# ESP32_with_USBC.net
KiCad netlist of a schematic drawn in Altium Designer
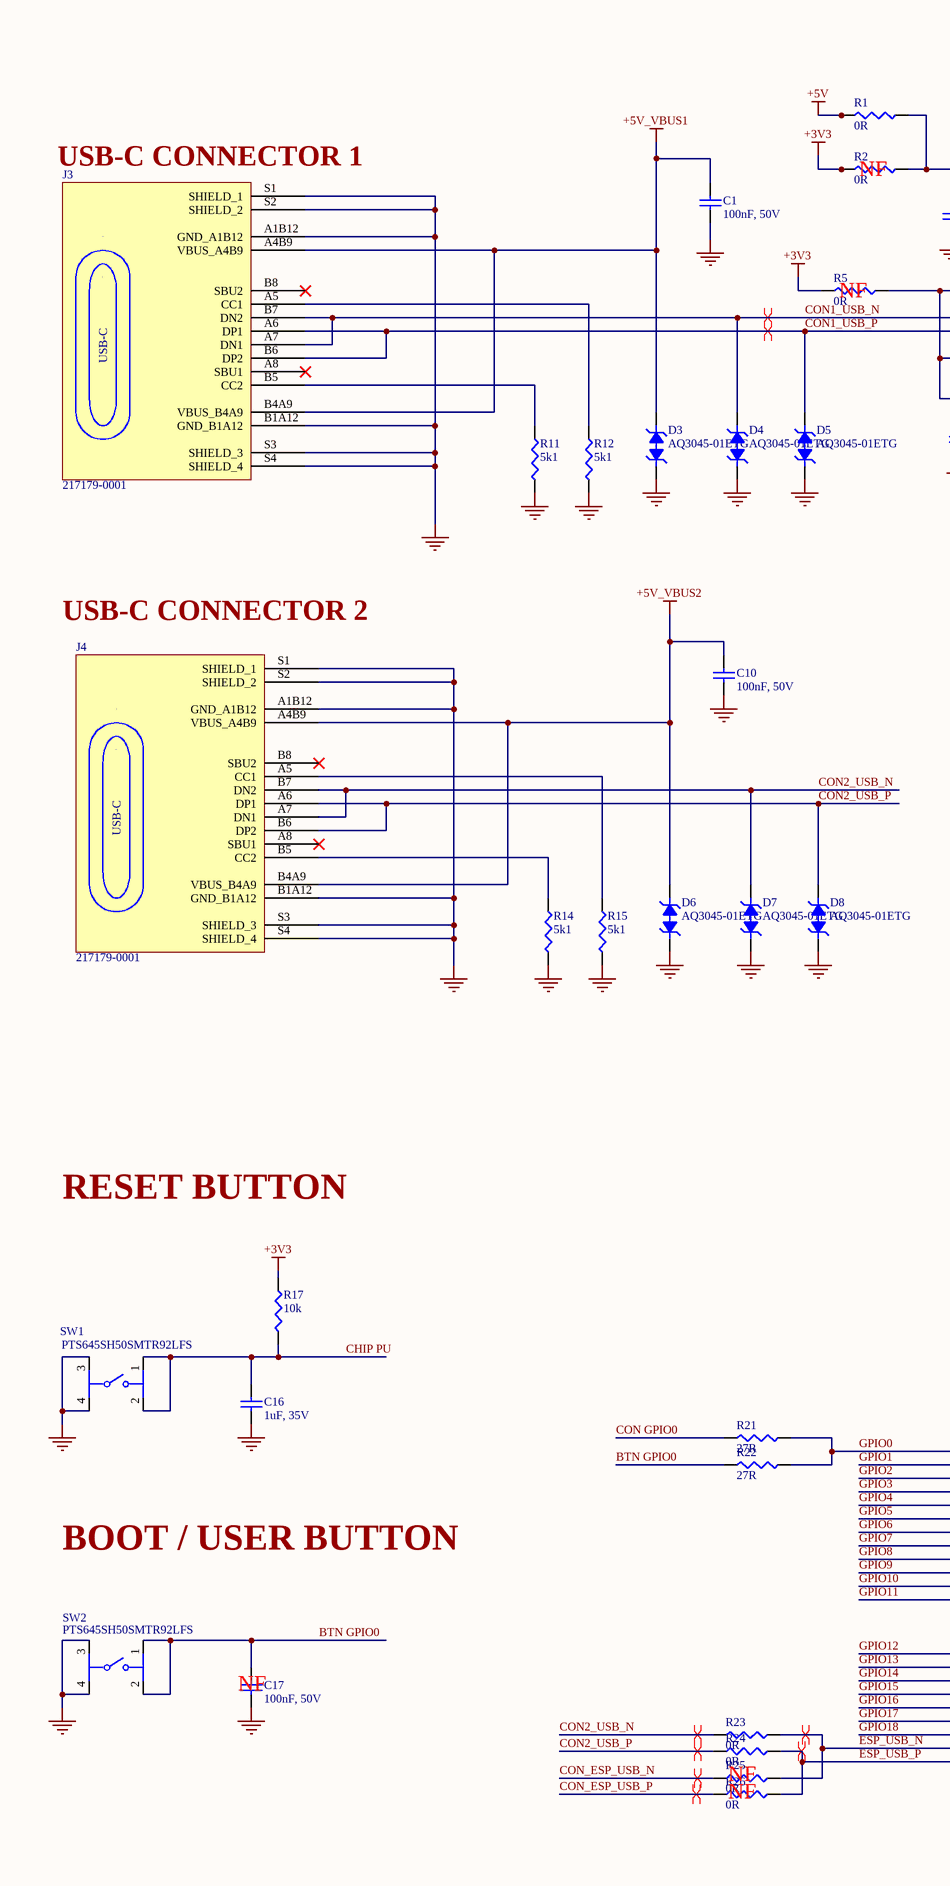
[diagram p0: ESP32 with USBC.SchDoc, left]
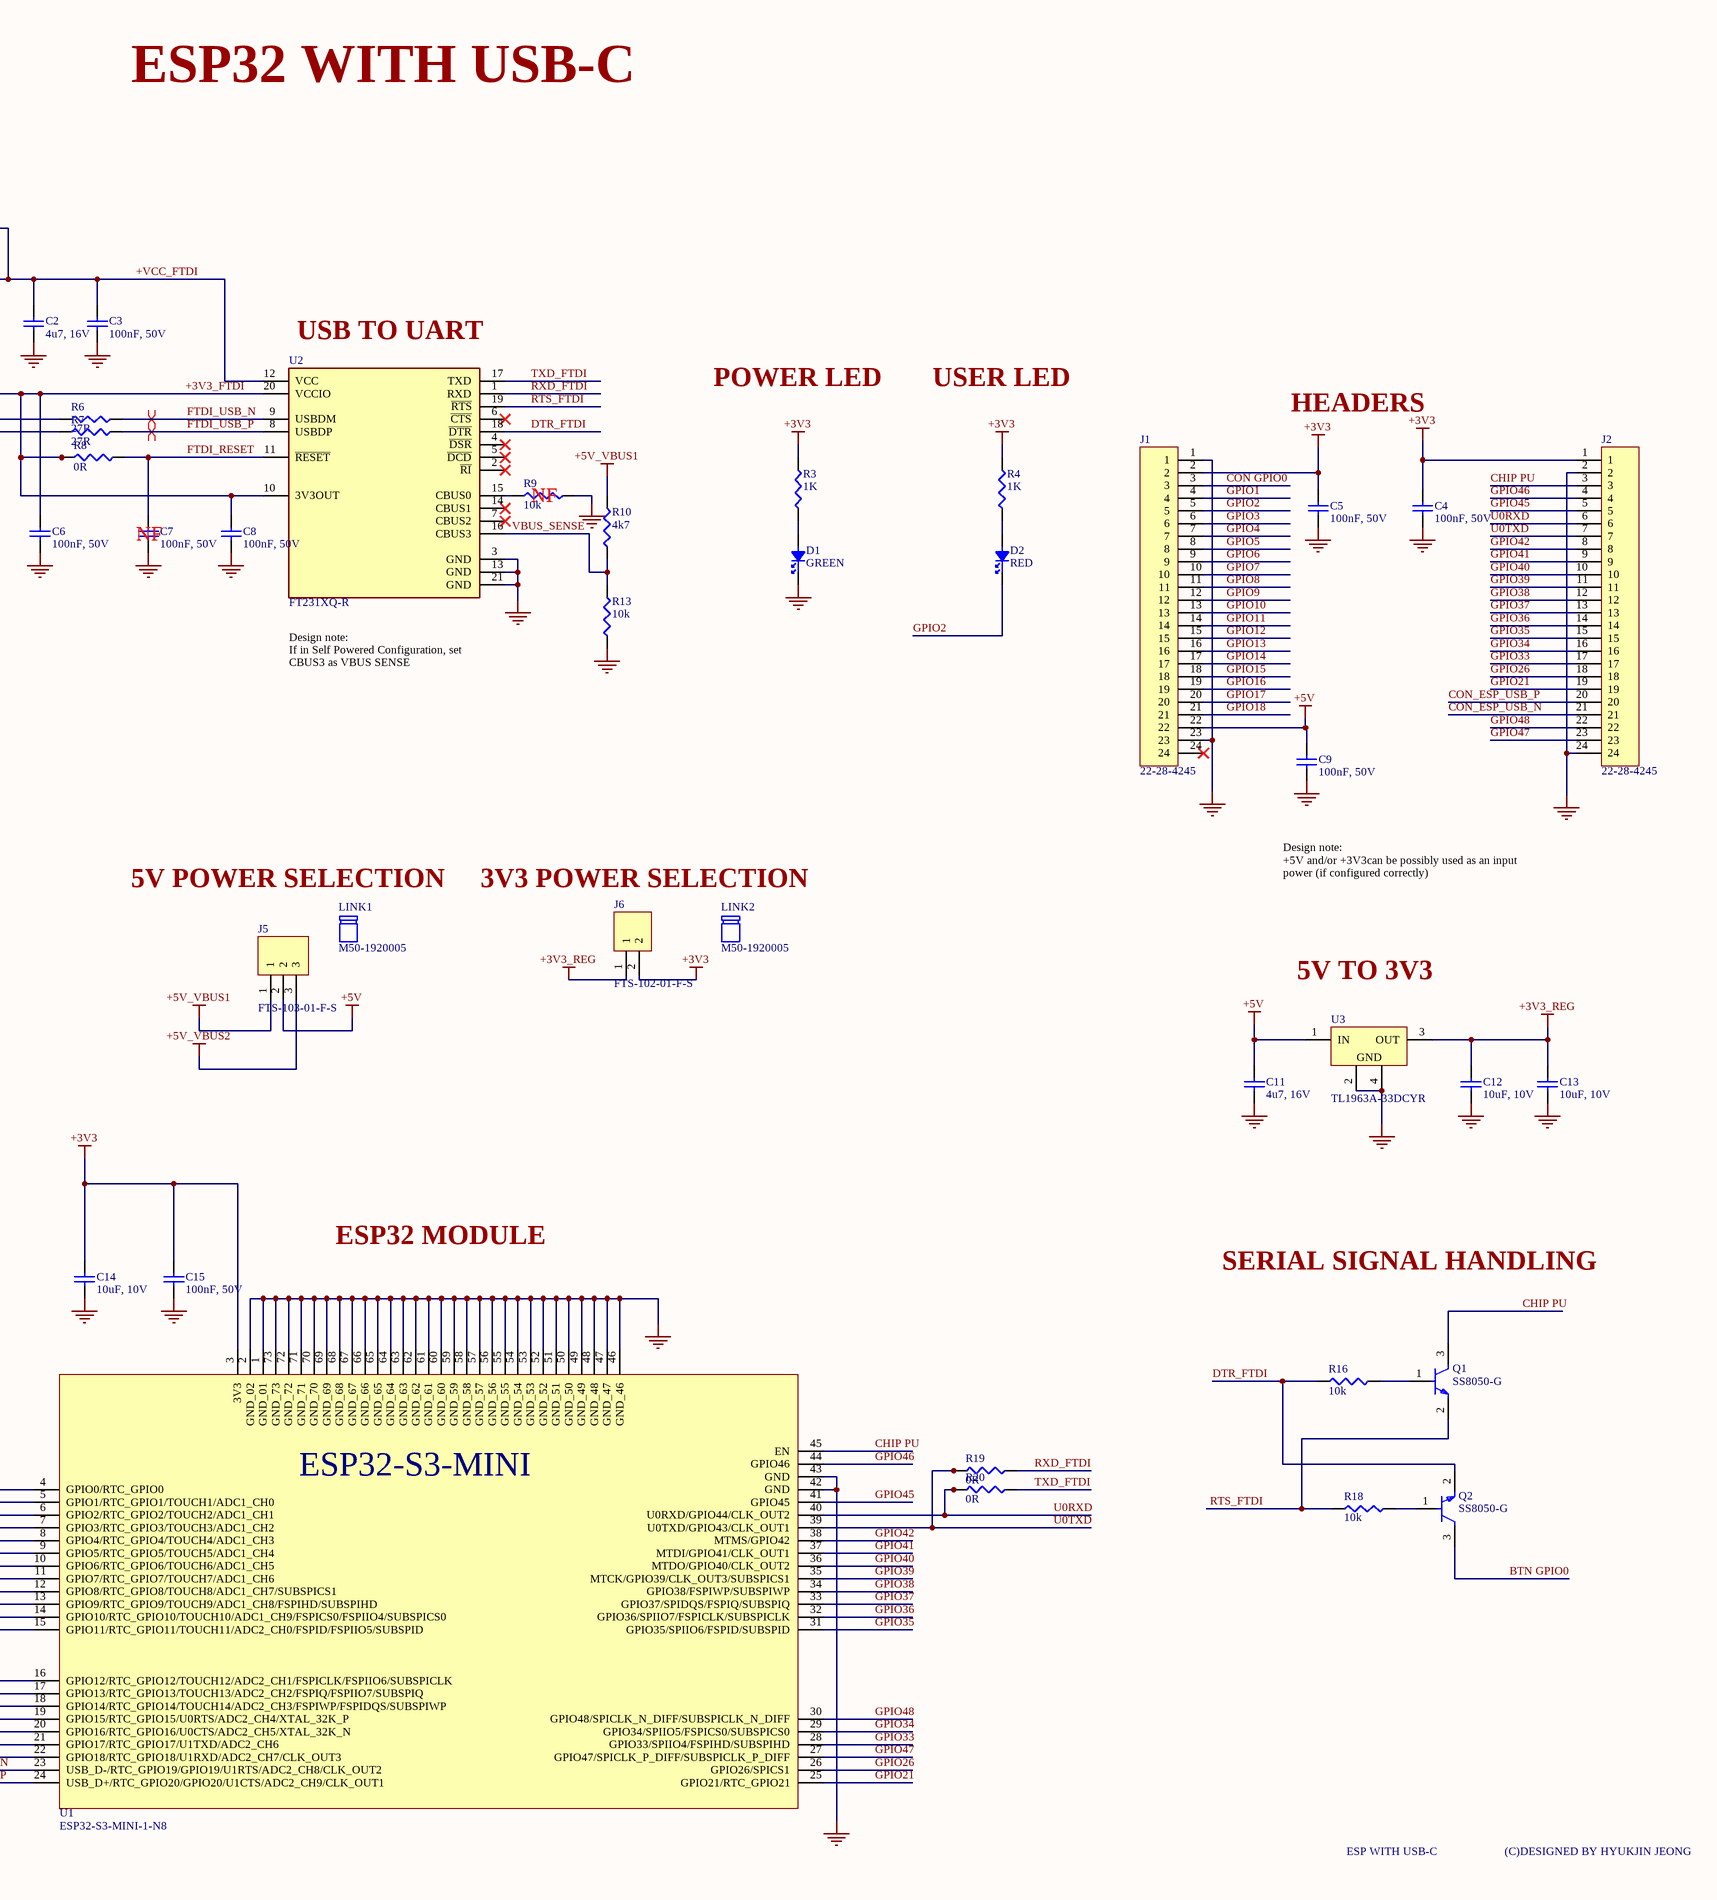
[diagram p1: ESP32 with USBC.SchDoc, right]

(export (version "E")
  (design (tool "Eeschema 10.0.6"))
  (components
    (comp (ref "C1")
      (value "100nF, 50V")
      (footprint "CAPC1005X65N")
      (description "CAP CER 0.1UF 50V X7R 0402")
      (fields
        (field (name "MANUFACTURER") "Samsung Electro-Mechanics")
        (field (name "MANUFACTURER PART NUMBER") "CL05B104KB54PNC")
      )
      (libsource (lib "Schlib") (part "CL05B104KB54PNC"))
    )
    (comp (ref "C2")
      (value "4u7, 16V")
      (footprint "CAPC1005X65N")
      (description "CAP CER 4.7UF 16V X5R 0402")
      (fields
        (field (name "MANUFACTURER") "Samsung Electro-Mechanics")
        (field (name "MANUFACTURER PART NUMBER") "CL05A475MO5NUNC")
      )
      (libsource (lib "Schlib") (part "CL05A475MO5NUNC"))
    )
    (comp (ref "C3")
      (value "100nF, 50V")
      (footprint "CAPC1005X65N")
      (description "CAP CER 0.1UF 50V X7R 0402")
      (fields
        (field (name "MANUFACTURER") "Samsung Electro-Mechanics")
        (field (name "MANUFACTURER PART NUMBER") "CL05B104KB54PNC")
      )
      (libsource (lib "Schlib") (part "CL05B104KB54PNC"))
    )
    (comp (ref "C4")
      (value "100nF, 50V")
      (footprint "CAPC1005X65N")
      (description "CAP CER 0.1UF 50V X7R 0402")
      (fields
        (field (name "MANUFACTURER") "Samsung Electro-Mechanics")
        (field (name "MANUFACTURER PART NUMBER") "CL05B104KB54PNC")
      )
      (libsource (lib "Schlib") (part "CL05B104KB54PNC"))
    )
    (comp (ref "C5")
      (value "100nF, 50V")
      (footprint "CAPC1005X65N")
      (description "CAP CER 0.1UF 50V X7R 0402")
      (fields
        (field (name "MANUFACTURER") "Samsung Electro-Mechanics")
        (field (name "MANUFACTURER PART NUMBER") "CL05B104KB54PNC")
      )
      (libsource (lib "Schlib") (part "CL05B104KB54PNC"))
    )
    (comp (ref "C6")
      (value "100nF, 50V")
      (footprint "CAPC1005X65N")
      (description "CAP CER 0.1UF 50V X7R 0402")
      (fields
        (field (name "MANUFACTURER") "Samsung Electro-Mechanics")
        (field (name "MANUFACTURER PART NUMBER") "CL05B104KB54PNC")
      )
      (libsource (lib "Schlib") (part "CL05B104KB54PNC"))
    )
    (comp (ref "C7")
      (value "100nF, 50V")
      (footprint "CAPC1005X65N")
      (description "CAP CER 0.1UF 50V X7R 0402")
      (fields
        (field (name "MANUFACTURER") "Samsung Electro-Mechanics")
        (field (name "MANUFACTURER PART NUMBER") "CL05B104KB54PNC")
      )
      (libsource (lib "Schlib") (part "CL05B104KB54PNC"))
    )
    (comp (ref "C8")
      (value "100nF, 50V")
      (footprint "CAPC1005X65N")
      (description "CAP CER 0.1UF 50V X7R 0402")
      (fields
        (field (name "MANUFACTURER") "Samsung Electro-Mechanics")
        (field (name "MANUFACTURER PART NUMBER") "CL05B104KB54PNC")
      )
      (libsource (lib "Schlib") (part "CL05B104KB54PNC"))
    )
    (comp (ref "C9")
      (value "100nF, 50V")
      (footprint "CAPC1005X65N")
      (description "CAP CER 0.1UF 50V X7R 0402")
      (fields
        (field (name "MANUFACTURER") "Samsung Electro-Mechanics")
        (field (name "MANUFACTURER PART NUMBER") "CL05B104KB54PNC")
      )
      (libsource (lib "Schlib") (part "CL05B104KB54PNC"))
    )
    (comp (ref "C10")
      (value "100nF, 50V")
      (footprint "CAPC1005X65N")
      (description "CAP CER 0.1UF 50V X7R 0402")
      (fields
        (field (name "MANUFACTURER") "Samsung Electro-Mechanics")
        (field (name "MANUFACTURER PART NUMBER") "CL05B104KB54PNC")
      )
      (libsource (lib "Schlib") (part "CL05B104KB54PNC"))
    )
    (comp (ref "C11")
      (value "4u7, 16V")
      (footprint "CAPC1005X65N")
      (description "CAP CER 4.7UF 16V X5R 0402")
      (fields
        (field (name "MANUFACTURER") "Samsung Electro-Mechanics")
        (field (name "MANUFACTURER PART NUMBER") "CL05A475MO5NUNC")
      )
      (libsource (lib "Schlib") (part "CL05A475MO5NUNC"))
    )
    (comp (ref "C12")
      (value "10uF, 10V")
      (footprint "CAPC1005X65N")
      (description "CAP CER 10UF 10V X5R 0402")
      (fields
        (field (name "MANUFACTURER") "Samsung Electro-Mechanics")
        (field (name "MANUFACTURER PART NUMBER") "CL05A106MP8NUB8")
      )
      (libsource (lib "Schlib") (part "CL05A106MP8NUB8"))
    )
    (comp (ref "C13")
      (value "10uF, 10V")
      (footprint "CAPC1005X65N")
      (description "CAP CER 10UF 10V X5R 0402")
      (fields
        (field (name "MANUFACTURER") "Samsung Electro-Mechanics")
        (field (name "MANUFACTURER PART NUMBER") "CL05A106MP8NUB8")
      )
      (libsource (lib "Schlib") (part "CL05A106MP8NUB8"))
    )
    (comp (ref "C14")
      (value "10uF, 10V")
      (footprint "CAPC1005X65N")
      (description "CAP CER 10UF 10V X5R 0402")
      (fields
        (field (name "MANUFACTURER") "Samsung Electro-Mechanics")
        (field (name "MANUFACTURER PART NUMBER") "CL05A106MP8NUB8")
      )
      (libsource (lib "Schlib") (part "CL05A106MP8NUB8"))
    )
    (comp (ref "C15")
      (value "100nF, 50V")
      (footprint "CAPC1005X65N")
      (description "CAP CER 0.1UF 50V X7R 0402")
      (fields
        (field (name "MANUFACTURER") "Samsung Electro-Mechanics")
        (field (name "MANUFACTURER PART NUMBER") "CL05B104KB54PNC")
      )
      (libsource (lib "Schlib") (part "CL05B104KB54PNC"))
    )
    (comp (ref "C16")
      (value "1uF, 35V")
      (footprint "CAPC1005X65N")
      (description "CAP CER 1UF 35V X5R 0402")
      (fields
        (field (name "MANUFACTURER") "Samsung Electro-Mechanics")
        (field (name "MANUFACTURER PART NUMBER") "CL05A105KL5NRNC")
      )
      (libsource (lib "Schlib") (part "CL05A105KL5NRNC"))
    )
    (comp (ref "C17")
      (value "100nF, 50V")
      (footprint "CAPC1005X65N")
      (description "CAP CER 0.1UF 50V X7R 0402")
      (fields
        (field (name "MANUFACTURER") "Samsung Electro-Mechanics")
        (field (name "MANUFACTURER PART NUMBER") "CL05B104KB54PNC")
      )
      (libsource (lib "Schlib") (part "CL05B104KB54PNC"))
    )
    (comp (ref "D1")
      (value "GREEN")
      (footprint "LED0402G")
      (description "LED YLW-GRN 0402 SMD")
      (fields
        (field (name "MANUFACTURER") "Vishay")
        (field (name "MANUFACTURER PART NUMBER") "VLMG1500-GS08")
      )
      (libsource (lib "Schlib") (part "VLMG1500-GS08"))
    )
    (comp (ref "D2")
      (value "RED")
      (footprint "LED0402R")
      (description "LED RED 0402 SMD")
      (fields
        (field (name "MANUFACTURER") "Vishay")
        (field (name "MANUFACTURER PART NUMBER") "VLMS1500-GS08")
      )
      (libsource (lib "Schlib") (part "VLMS1500-GS08"))
    )
    (comp (ref "D3")
      (value "AQ3045-01ETG")
      (footprint "SOD882")
      (description "TVS DIODE 5.3VWM 12VC SOD882")
      (fields (field (name "MANUFACTURER") "Littelfuse") (field (name "LCSC PART NUMBER") "C3710326"))
      (libsource (lib "Schlib") (part "AQ3045-01ETG"))
    )
    (comp (ref "D4")
      (value "AQ3045-01ETG")
      (footprint "SOD882")
      (description "TVS DIODE 5.3VWM 12VC SOD882")
      (fields (field (name "MANUFACTURER") "Littelfuse") (field (name "LCSC PART NUMBER") "C3710326"))
      (libsource (lib "Schlib") (part "AQ3045-01ETG"))
    )
    (comp (ref "D5")
      (value "AQ3045-01ETG")
      (footprint "SOD882")
      (description "TVS DIODE 5.3VWM 12VC SOD882")
      (fields (field (name "MANUFACTURER") "Littelfuse") (field (name "LCSC PART NUMBER") "C3710326"))
      (libsource (lib "Schlib") (part "AQ3045-01ETG"))
    )
    (comp (ref "D6")
      (value "AQ3045-01ETG")
      (footprint "SOD882")
      (description "TVS DIODE 5.3VWM 12VC SOD882")
      (fields (field (name "MANUFACTURER") "Littelfuse") (field (name "LCSC PART NUMBER") "C3710326"))
      (libsource (lib "Schlib") (part "AQ3045-01ETG"))
    )
    (comp (ref "D7")
      (value "AQ3045-01ETG")
      (footprint "SOD882")
      (description "TVS DIODE 5.3VWM 12VC SOD882")
      (fields (field (name "MANUFACTURER") "Littelfuse") (field (name "LCSC PART NUMBER") "C3710326"))
      (libsource (lib "Schlib") (part "AQ3045-01ETG"))
    )
    (comp (ref "D8")
      (value "AQ3045-01ETG")
      (footprint "SOD882")
      (description "TVS DIODE 5.3VWM 12VC SOD882")
      (fields (field (name "MANUFACTURER") "Littelfuse") (field (name "LCSC PART NUMBER") "C3710326"))
      (libsource (lib "Schlib") (part "AQ3045-01ETG"))
    )
    (comp (ref "J1")
      (value "22-28-4245")
      (footprint "HDR_1X24_2.54MM")
      (description "CONN HEADER VERT 24POS 2.54MM")
      (fields (field (name "MANUFACTURER") "Molex") (field (name "LCSC PART NUMBER") "C7145888"))
      (libsource (lib "Schlib") (part "22-28-4245"))
    )
    (comp (ref "J2")
      (value "22-28-4245")
      (footprint "HDR_1X24_2.54MM")
      (description "CONN HEADER VERT 24POS 2.54MM")
      (fields (field (name "MANUFACTURER") "Molex") (field (name "LCSC PART NUMBER") "C7145888"))
      (libsource (lib "") (part "22-28-4245_1"))
    )
    (comp (ref "J3")
      (value "217179-0001")
      (footprint "FP-2171790001-MFG")
      (description "CONN RCP USB2.0 TYP C 24P SMD RA")
      (fields (field (name "MANUFACTURER") "Molex") (field (name "LCSC PART NUMBER") "C3197684"))
      (libsource (lib "Schlib") (part "217179-0001"))
    )
    (comp (ref "J4")
      (value "217179-0001")
      (footprint "FP-2171790001-MFG")
      (description "CONN RCP USB2.0 TYP C 24P SMD RA")
      (fields (field (name "MANUFACTURER") "Molex") (field (name "LCSC PART NUMBER") "C3197684"))
      (libsource (lib "Schlib") (part "217179-0001"))
    )
    (comp (ref "J5")
      (value "FTS-103-01-F-S")
      (footprint "HDR_1X3_1.27MM")
      (description "CONN HEADER VERT 3POS 1.27MM")
      (fields (field (name "MANUFACTURER") "Samtec") (field (name "LCSC PART NUMBER") "C3333578"))
      (libsource (lib "Schlib") (part "FTS-103-01-F-S"))
    )
    (comp (ref "J6")
      (value "FTS-102-01-F-S")
      (footprint "HDR_1X2_1.27MM")
      (description "CONN HEADER VERT 2POS 1.27MM")
      (fields (field (name "MANUFACTURER") "Samtec") (field (name "LCSC PART NUMBER") "C6045317"))
      (libsource (lib "Schlib") (part "FTS-102-01-F-S"))
    )
    (comp (ref "LINK1")
      (value "M50-1920005")
      (description "CONN SHUNT 1.27MM RED")
      (fields (field (name "MANUFACTURER") "Harwin") (field (name "LCSC PART NUMBER") "C6985646"))
      (libsource (lib "Schlib") (part "M50-1920005"))
    )
    (comp (ref "LINK2")
      (value "M50-1920005")
      (description "CONN SHUNT 1.27MM RED")
      (fields (field (name "MANUFACTURER") "Harwin") (field (name "LCSC PART NUMBER") "C6985646"))
      (libsource (lib "Schlib") (part "M50-1920005"))
    )
    (comp (ref "Q1")
      (value "SS8050-G")
      (footprint "FP-SS8050-G-IPC_B")
      (description "TRANS NPN 25V 1.5A SOT-23-3")
      (fields (field (name "MANUFACTURER") "Comchip") (field (name "LCSC PART NUMBER") "C164886"))
      (libsource (lib "Schlib") (part "SS8050-G"))
    )
    (comp (ref "Q2")
      (value "SS8050-G")
      (footprint "FP-SS8050-G-IPC_B")
      (description "TRANS NPN 25V 1.5A SOT-23-3")
      (fields (field (name "MANUFACTURER") "Comchip") (field (name "LCSC PART NUMBER") "C164886"))
      (libsource (lib "Schlib") (part "SS8050-G"))
    )
    (comp (ref "R1")
      (value "0R")
      (footprint "RESC1005X37N")
      (description "RES 0 OHM JUMPER 1/16W 0402")
      (fields
        (field (name "MANUFACTURER") "Yageo Group")
        (field (name "MANUFACTURER PART NUMBER") "RC0402JR-070RL")
      )
      (libsource (lib "Schlib") (part "RC0402JR-070RL"))
    )
    (comp (ref "R2")
      (value "0R")
      (footprint "RESC1005X37N")
      (description "RES 0 OHM JUMPER 1/16W 0402")
      (fields
        (field (name "MANUFACTURER") "Yageo Group")
        (field (name "MANUFACTURER PART NUMBER") "RC0402JR-070RL")
      )
      (libsource (lib "Schlib") (part "RC0402JR-070RL"))
    )
    (comp (ref "R3")
      (value "1K")
      (footprint "RESC1005X37N")
      (description "RES 1K OHM 1% 1/16W 0402")
      (fields
        (field (name "MANUFACTURER") "Yageo Group")
        (field (name "MANUFACTURER PART NUMBER") "RC0402FR-0710KL")
      )
      (libsource (lib "Schlib") (part "RC0402FR-0710KL"))
    )
    (comp (ref "R4")
      (value "1K")
      (footprint "RESC1005X37N")
      (description "RES 1K OHM 1% 1/16W 0402")
      (fields
        (field (name "MANUFACTURER") "Yageo Group")
        (field (name "MANUFACTURER PART NUMBER") "RC0402FR-0710KL")
      )
      (libsource (lib "Schlib") (part "RC0402FR-0710KL"))
    )
    (comp (ref "R5")
      (value "0R")
      (footprint "RESC1005X37N")
      (description "RES 0 OHM JUMPER 1/16W 0402")
      (fields
        (field (name "MANUFACTURER") "Yageo Group")
        (field (name "MANUFACTURER PART NUMBER") "RC0402JR-070RL")
      )
      (libsource (lib "Schlib") (part "RC0402JR-070RL"))
    )
    (comp (ref "R6")
      (value "27R")
      (footprint "RESC1005X37N")
      (description "RES 27 OHM 1% 1/16W 0402")
      (fields
        (field (name "MANUFACTURER") "Yageo Group")
        (field (name "MANUFACTURER PART NUMBER") "RC0402FR-0727RL")
      )
      (libsource (lib "Schlib") (part "RC0402FR-0727RL"))
    )
    (comp (ref "R7")
      (value "27R")
      (footprint "RESC1005X37N")
      (description "RES 27 OHM 1% 1/16W 0402")
      (fields
        (field (name "MANUFACTURER") "Yageo Group")
        (field (name "MANUFACTURER PART NUMBER") "RC0402FR-0727RL")
      )
      (libsource (lib "Schlib") (part "RC0402FR-0727RL"))
    )
    (comp (ref "R8")
      (value "0R")
      (footprint "RESC1005X37N")
      (description "RES 0 OHM JUMPER 1/16W 0402")
      (fields
        (field (name "MANUFACTURER") "Yageo Group")
        (field (name "MANUFACTURER PART NUMBER") "RC0402JR-070RL")
      )
      (libsource (lib "Schlib") (part "RC0402JR-070RL"))
    )
    (comp (ref "R9")
      (value "10k")
      (footprint "RESC1005X37N")
      (description "RES SMD 10K OHM 1% 1/16W 0402")
      (fields
        (field (name "MANUFACTURER") "Yageo Group")
        (field (name "MANUFACTURER PART NUMBER") "AC0402FR-0710KL")
      )
      (libsource (lib "Schlib") (part "AC0402FR-0710KL"))
    )
    (comp (ref "R10")
      (value "4k7")
      (footprint "RESC1005X37N")
      (description "RES 4.7K OHM 1% 1/16W 0402")
      (fields
        (field (name "MANUFACTURER") "Yageo Group")
        (field (name "MANUFACTURER PART NUMBER") "RC0402FR-074K7L")
      )
      (libsource (lib "Schlib") (part "RC0402FR-074K7L"))
    )
    (comp (ref "R11")
      (value "5k1")
      (footprint "RESC1005X37N")
      (fields
        (field (name "MANUFACTURER") "Yageo Group")
        (field (name "MANUFACTURER PART NUMBER") "AC0402FR-075K1L")
        (field (name "TOLERANCE") "1%")
      )
      (libsource (lib "Schlib") (part "AC0402FR-075K1L"))
    )
    (comp (ref "R12")
      (value "5k1")
      (footprint "RESC1005X37N")
      (fields
        (field (name "MANUFACTURER") "Yageo Group")
        (field (name "MANUFACTURER PART NUMBER") "AC0402FR-075K1L")
        (field (name "TOLERANCE") "1%")
      )
      (libsource (lib "Schlib") (part "AC0402FR-075K1L"))
    )
    (comp (ref "R13")
      (value "10k")
      (footprint "RESC1005X37N")
      (description "RES SMD 10K OHM 1% 1/16W 0402")
      (fields
        (field (name "MANUFACTURER") "Yageo Group")
        (field (name "MANUFACTURER PART NUMBER") "AC0402FR-0710KL")
      )
      (libsource (lib "Schlib") (part "AC0402FR-0710KL"))
    )
    (comp (ref "R14")
      (value "5k1")
      (footprint "RESC1005X37N")
      (fields
        (field (name "MANUFACTURER") "Yageo Group")
        (field (name "MANUFACTURER PART NUMBER") "AC0402FR-075K1L")
        (field (name "TOLERANCE") "1%")
      )
      (libsource (lib "Schlib") (part "AC0402FR-075K1L"))
    )
    (comp (ref "R15")
      (value "5k1")
      (footprint "RESC1005X37N")
      (fields
        (field (name "MANUFACTURER") "Yageo Group")
        (field (name "MANUFACTURER PART NUMBER") "AC0402FR-075K1L")
        (field (name "TOLERANCE") "1%")
      )
      (libsource (lib "Schlib") (part "AC0402FR-075K1L"))
    )
    (comp (ref "R16")
      (value "10k")
      (footprint "RESC1005X37N")
      (description "RES SMD 10K OHM 1% 1/16W 0402")
      (fields
        (field (name "MANUFACTURER") "Yageo Group")
        (field (name "MANUFACTURER PART NUMBER") "AC0402FR-0710KL")
      )
      (libsource (lib "Schlib") (part "AC0402FR-0710KL"))
    )
    (comp (ref "R17")
      (value "10k")
      (footprint "RESC1005X37N")
      (description "RES SMD 10K OHM 1% 1/16W 0402")
      (fields
        (field (name "MANUFACTURER") "Yageo Group")
        (field (name "MANUFACTURER PART NUMBER") "AC0402FR-0710KL")
      )
      (libsource (lib "Schlib") (part "AC0402FR-0710KL"))
    )
    (comp (ref "R18")
      (value "10k")
      (footprint "RESC1005X37N")
      (description "RES SMD 10K OHM 1% 1/16W 0402")
      (fields
        (field (name "MANUFACTURER") "Yageo Group")
        (field (name "MANUFACTURER PART NUMBER") "AC0402FR-0710KL")
      )
      (libsource (lib "Schlib") (part "AC0402FR-0710KL"))
    )
    (comp (ref "R19")
      (value "0R")
      (footprint "RESC1005X37N")
      (description "RES 0 OHM JUMPER 1/16W 0402")
      (fields
        (field (name "MANUFACTURER") "Yageo Group")
        (field (name "MANUFACTURER PART NUMBER") "RC0402JR-070RL")
      )
      (libsource (lib "Schlib") (part "RC0402JR-070RL"))
    )
    (comp (ref "R20")
      (value "0R")
      (footprint "RESC1005X37N")
      (description "RES 0 OHM JUMPER 1/16W 0402")
      (fields
        (field (name "MANUFACTURER") "Yageo Group")
        (field (name "MANUFACTURER PART NUMBER") "RC0402JR-070RL")
      )
      (libsource (lib "Schlib") (part "RC0402JR-070RL"))
    )
    (comp (ref "R21")
      (value "27R")
      (footprint "RESC1005X37N")
      (description "RES 27 OHM 1% 1/16W 0402")
      (fields
        (field (name "MANUFACTURER") "Yageo Group")
        (field (name "MANUFACTURER PART NUMBER") "RC0402FR-0727RL")
      )
      (libsource (lib "Schlib") (part "RC0402FR-0727RL"))
    )
    (comp (ref "R22")
      (value "27R")
      (footprint "RESC1005X37N")
      (description "RES 27 OHM 1% 1/16W 0402")
      (fields
        (field (name "MANUFACTURER") "Yageo Group")
        (field (name "MANUFACTURER PART NUMBER") "RC0402FR-0727RL")
      )
      (libsource (lib "Schlib") (part "RC0402FR-0727RL"))
    )
    (comp (ref "R23")
      (value "0R")
      (footprint "RESC1005X37N")
      (description "RES 0 OHM JUMPER 1/16W 0402")
      (fields
        (field (name "MANUFACTURER") "Yageo Group")
        (field (name "MANUFACTURER PART NUMBER") "RC0402JR-070RL")
      )
      (libsource (lib "Schlib") (part "RC0402JR-070RL"))
    )
    (comp (ref "R24")
      (value "0R")
      (footprint "RESC1005X37N")
      (description "RES 0 OHM JUMPER 1/16W 0402")
      (fields
        (field (name "MANUFACTURER") "Yageo Group")
        (field (name "MANUFACTURER PART NUMBER") "RC0402JR-070RL")
      )
      (libsource (lib "Schlib") (part "RC0402JR-070RL"))
    )
    (comp (ref "R25")
      (value "0R")
      (footprint "RESC1005X37N")
      (description "RES 0 OHM JUMPER 1/16W 0402")
      (fields
        (field (name "MANUFACTURER") "Yageo Group")
        (field (name "MANUFACTURER PART NUMBER") "RC0402JR-070RL")
      )
      (libsource (lib "Schlib") (part "RC0402JR-070RL"))
    )
    (comp (ref "R26")
      (value "0R")
      (footprint "RESC1005X37N")
      (description "RES 0 OHM JUMPER 1/16W 0402")
      (fields
        (field (name "MANUFACTURER") "Yageo Group")
        (field (name "MANUFACTURER PART NUMBER") "RC0402JR-070RL")
      )
      (libsource (lib "Schlib") (part "RC0402JR-070RL"))
    )
    (comp (ref "SW1")
      (value "PTS645SH50SMTR92LFS")
      (footprint "FP-PTS645SH50SMTR92LFS-MFG")
      (description "SWITCH TACTILE SPST-NO 0.05A 12V")
      (fields (field (name "MANUFACTURER") "C&K Components") (field (name "LCSC PART NUMBER") "C221869"))
      (libsource (lib "Schlib") (part "PTS645SH50SMTR92LFS"))
    )
    (comp (ref "SW2")
      (value "PTS645SH50SMTR92LFS")
      (footprint "FP-PTS645SH50SMTR92LFS-MFG")
      (description "SWITCH TACTILE SPST-NO 0.05A 12V")
      (fields (field (name "MANUFACTURER") "C&K Components") (field (name "LCSC PART NUMBER") "C221869"))
      (libsource (lib "Schlib") (part "PTS645SH50SMTR92LFS"))
    )
    (comp (ref "U1")
      (value "ESP32-S3-MINI-1-N8")
      (footprint "XCVR_ESP32-S3-MINI-1-N8")
      (description "SMD Module, ESP-32-S3FN8, 8 mb Sp")
      (fields (field (name "MANUFACTURER") "Espressif Systems") (field (name "LCSC PART NUMBER") "C2913206"))
      (libsource (lib "Schlib") (part "ESP32-S3-MINI-1-N8"))
    )
    (comp (ref "U2")
      (value "FT231XQ-R")
      (footprint "FP-QFN-20-IPC_B")
      (description "IC USB SERIAL FULL UART 20QFN")
      (fields (field (name "MANUFACTURER") "FTDI") (field (name "LCSC PART NUMBER") "C132159"))
      (libsource (lib "Schlib") (part "FT231XQ-R"))
    )
    (comp (ref "U3")
      (value "TL1963A-33DCYR")
      (footprint "DCY0004A_N")
      (description "IC REG LIN 3.3V 1.5A SOT-223-4")
      (fields (field (name "MANUFACTURER") "Texas Instruments") (field (name "LCSC PART NUMBER") "C181262"))
      (libsource (lib "Schlib") (part "TL1963A-33DCYR"))
    )
  )
  (nets
    (net (code "1") (name "+3V3") (class "Default")
      (node (ref "C14") (pin "2") (pinfunction "2_2") (pintype "passive"))
      (node (ref "C15") (pin "2") (pinfunction "2_2") (pintype "passive"))
      (node (ref "C4") (pin "2") (pinfunction "2_2") (pintype "passive"))
      (node (ref "C5") (pin "2") (pinfunction "2_2") (pintype "passive"))
      (node (ref "J1") (pin "2") (pinfunction "2_2") (pintype "passive"))
      (node (ref "J2") (pin "1") (pinfunction "1_1") (pintype "passive"))
      (node (ref "J6") (pin "2") (pinfunction "2_2") (pintype "passive"))
      (node (ref "R17") (pin "2") (pinfunction "2_2") (pintype "passive"))
      (node (ref "R2") (pin "1") (pinfunction "1_1") (pintype "passive"))
      (node (ref "R3") (pin "2") (pinfunction "2_2") (pintype "passive"))
      (node (ref "R4") (pin "2") (pinfunction "2_2") (pintype "passive"))
      (node (ref "R5") (pin "1") (pinfunction "1_1") (pintype "passive"))
      (node (ref "U1") (pin "3") (pinfunction "3V3_3") (pintype "passive"))
    )
    (net (code "2") (name "+3V3_REG") (class "Default")
      (node (ref "C12") (pin "2") (pinfunction "2_2") (pintype "passive"))
      (node (ref "C13") (pin "2") (pinfunction "2_2") (pintype "passive"))
      (node (ref "J6") (pin "1") (pinfunction "1_1") (pintype "passive"))
      (node (ref "U3") (pin "3") (pinfunction "OUT_3") (pintype "power_in"))
    )
    (net (code "3") (name "+5V") (class "Default")
      (node (ref "C11") (pin "2") (pinfunction "2_2") (pintype "passive"))
      (node (ref "C9") (pin "2") (pinfunction "2_2") (pintype "passive"))
      (node (ref "J1") (pin "22") (pinfunction "22_22") (pintype "passive"))
      (node (ref "J5") (pin "2") (pinfunction "2_2") (pintype "passive"))
      (node (ref "R1") (pin "1") (pinfunction "1_1") (pintype "passive"))
      (node (ref "U3") (pin "1") (pinfunction "IN_1") (pintype "power_in"))
    )
    (net (code "4") (name "+5V_VBUS1") (class "Default")
      (node (ref "C1") (pin "2") (pinfunction "2_2") (pintype "passive"))
      (node (ref "D3") (pin "2") (pinfunction "2_2") (pintype "passive"))
      (node (ref "J3") (pin "A4B9") (pinfunction "VBUS_A4B9_A4B9") (pintype "passive"))
      (node (ref "J3") (pin "B4A9") (pinfunction "VBUS_B4A9_B4A9") (pintype "passive"))
      (node (ref "J5") (pin "1") (pinfunction "1_1") (pintype "passive"))
      (node (ref "R10") (pin "2") (pinfunction "2_2") (pintype "passive"))
    )
    (net (code "5") (name "+5V_VBUS2") (class "Default")
      (node (ref "C10") (pin "2") (pinfunction "2_2") (pintype "passive"))
      (node (ref "D6") (pin "2") (pinfunction "2_2") (pintype "passive"))
      (node (ref "J4") (pin "A4B9") (pinfunction "VBUS_A4B9_A4B9") (pintype "passive"))
      (node (ref "J4") (pin "B4A9") (pinfunction "VBUS_B4A9_B4A9") (pintype "passive"))
      (node (ref "J5") (pin "3") (pinfunction "3_3") (pintype "passive"))
    )
    (net (code "6") (name "/+3V3_FTDI") (class "Default")
      (node (ref "C6") (pin "2") (pinfunction "2_2") (pintype "passive"))
      (node (ref "C8") (pin "2") (pinfunction "2_2") (pintype "passive"))
      (node (ref "R5") (pin "2") (pinfunction "2_2") (pintype "passive"))
      (node (ref "R8") (pin "1") (pinfunction "1_1") (pintype "passive"))
      (node (ref "U2") (pin "10") (pinfunction "3V3OUT_10") (pintype "passive"))
      (node (ref "U2") (pin "20") (pinfunction "VCCIO_20") (pintype "passive"))
    )
    (net (code "7") (name "/+VCC_FTDI") (class "Default")
      (node (ref "C2") (pin "2") (pinfunction "2_2") (pintype "passive"))
      (node (ref "C3") (pin "2") (pinfunction "2_2") (pintype "passive"))
      (node (ref "R1") (pin "2") (pinfunction "2_2") (pintype "passive"))
      (node (ref "R2") (pin "2") (pinfunction "2_2") (pintype "passive"))
      (node (ref "U2") (pin "12") (pinfunction "VCC_12") (pintype "passive"))
    )
    (net (code "8") (name "/BTN GPIO0") (class "Default")
      (node (ref "C17") (pin "2") (pinfunction "2_2") (pintype "passive"))
      (node (ref "Q2") (pin "3") (pinfunction "C_3") (pintype "passive"))
      (node (ref "R22") (pin "1") (pinfunction "1_1") (pintype "passive"))
      (node (ref "SW2") (pin "1") (pinfunction "1_1") (pintype "passive"))
      (node (ref "SW2") (pin "2") (pinfunction "2_2") (pintype "passive"))
    )
    (net (code "9") (name "/CHIP PU") (class "Default")
      (node (ref "C16") (pin "2") (pinfunction "2_2") (pintype "passive"))
      (node (ref "J2") (pin "3") (pinfunction "3_3") (pintype "passive"))
      (node (ref "Q1") (pin "3") (pinfunction "C_3") (pintype "passive"))
      (node (ref "R17") (pin "1") (pinfunction "1_1") (pintype "passive"))
      (node (ref "SW1") (pin "1") (pinfunction "1_1") (pintype "passive"))
      (node (ref "SW1") (pin "2") (pinfunction "2_2") (pintype "passive"))
      (node (ref "U1") (pin "45") (pinfunction "EN_45") (pintype "passive"))
    )
    (net (code "10") (name "/CON GPIO0") (class "Default")
      (node (ref "J1") (pin "3") (pinfunction "3_3") (pintype "passive"))
      (node (ref "R21") (pin "1") (pinfunction "1_1") (pintype "passive"))
    )
    (net (code "11") (name "/CON1_USB_N") (class "Default")
      (node (ref "D4") (pin "2") (pinfunction "2_2") (pintype "passive"))
      (node (ref "J3") (pin "A7") (pinfunction "DN1_A7") (pintype "passive"))
      (node (ref "J3") (pin "B7") (pinfunction "DN2_B7") (pintype "passive"))
      (node (ref "R6") (pin "1") (pinfunction "1_1") (pintype "passive"))
    )
    (net (code "12") (name "/CON1_USB_P") (class "Default")
      (node (ref "D5") (pin "2") (pinfunction "2_2") (pintype "passive"))
      (node (ref "J3") (pin "A6") (pinfunction "DP1_A6") (pintype "passive"))
      (node (ref "J3") (pin "B6") (pinfunction "DP2_B6") (pintype "passive"))
      (node (ref "R7") (pin "1") (pinfunction "1_1") (pintype "passive"))
    )
    (net (code "13") (name "/CON2_USB_N") (class "Default")
      (node (ref "D7") (pin "2") (pinfunction "2_2") (pintype "passive"))
      (node (ref "J4") (pin "A7") (pinfunction "DN1_A7") (pintype "passive"))
      (node (ref "J4") (pin "B7") (pinfunction "DN2_B7") (pintype "passive"))
      (node (ref "R23") (pin "1") (pinfunction "1_1") (pintype "passive"))
    )
    (net (code "14") (name "/CON2_USB_P") (class "Default")
      (node (ref "D8") (pin "2") (pinfunction "2_2") (pintype "passive"))
      (node (ref "J4") (pin "A6") (pinfunction "DP1_A6") (pintype "passive"))
      (node (ref "J4") (pin "B6") (pinfunction "DP2_B6") (pintype "passive"))
      (node (ref "R24") (pin "1") (pinfunction "1_1") (pintype "passive"))
    )
    (net (code "15") (name "/CON_ESP_USB_N") (class "Default")
      (node (ref "J2") (pin "21") (pinfunction "21_21") (pintype "passive"))
      (node (ref "R25") (pin "1") (pinfunction "1_1") (pintype "passive"))
    )
    (net (code "16") (name "/CON_ESP_USB_P") (class "Default")
      (node (ref "J2") (pin "20") (pinfunction "20_20") (pintype "passive"))
      (node (ref "R26") (pin "1") (pinfunction "1_1") (pintype "passive"))
    )
    (net (code "17") (name "/DTR_FTDI") (class "Default")
      (node (ref "Q2") (pin "2") (pinfunction "E_2") (pintype "passive"))
      (node (ref "R16") (pin "1") (pinfunction "1_1") (pintype "passive"))
      (node (ref "U2") (pin "18") (pinfunction "~{DTR}_18") (pintype "passive"))
    )
    (net (code "18") (name "/ESP_USB_N") (class "Default")
      (node (ref "R23") (pin "2") (pinfunction "2_2") (pintype "passive"))
      (node (ref "R25") (pin "2") (pinfunction "2_2") (pintype "passive"))
      (node (ref "U1") (pin "23") (pinfunction "USB_D-/RTC_GPIO19/GPIO19/U1RTS/ADC2_CH8/CLK_OUT2_23") (pintype "passive"))
    )
    (net (code "19") (name "/ESP_USB_P") (class "Default")
      (node (ref "R24") (pin "2") (pinfunction "2_2") (pintype "passive"))
      (node (ref "R26") (pin "2") (pinfunction "2_2") (pintype "passive"))
      (node (ref "U1") (pin "24") (pinfunction "USB_D+/RTC_GPIO20/GPIO20/U1CTS/ADC2_CH9/CLK_OUT1_24") (pintype "passive"))
    )
    (net (code "20") (name "/FTDI_RESET") (class "Default")
      (node (ref "C7") (pin "2") (pinfunction "2_2") (pintype "passive"))
      (node (ref "R8") (pin "2") (pinfunction "2_2") (pintype "passive"))
      (node (ref "U2") (pin "11") (pinfunction "~{RESET}_11") (pintype "passive"))
    )
    (net (code "21") (name "/FTDI_USB_N") (class "Default")
      (node (ref "R6") (pin "2") (pinfunction "2_2") (pintype "passive"))
      (node (ref "U2") (pin "9") (pinfunction "USBDM_9") (pintype "passive"))
    )
    (net (code "22") (name "/FTDI_USB_P") (class "Default")
      (node (ref "R7") (pin "2") (pinfunction "2_2") (pintype "passive"))
      (node (ref "U2") (pin "8") (pinfunction "USBDP_8") (pintype "passive"))
    )
    (net (code "23") (name "/GPIO0") (class "Default")
      (node (ref "R21") (pin "2") (pinfunction "2_2") (pintype "passive"))
      (node (ref "R22") (pin "2") (pinfunction "2_2") (pintype "passive"))
      (node (ref "U1") (pin "4") (pinfunction "GPIO0/RTC_GPIO0_4") (pintype "passive"))
    )
    (net (code "24") (name "/GPIO1") (class "Default")
      (node (ref "J1") (pin "4") (pinfunction "4_4") (pintype "passive"))
      (node (ref "U1") (pin "5") (pinfunction "GPIO1/RTC_GPIO1/TOUCH1/ADC1_CH0_5") (pintype "passive"))
    )
    (net (code "25") (name "/GPIO2") (class "Default")
      (node (ref "D2") (pin "1") (pinfunction "1_1") (pintype "passive"))
      (node (ref "J1") (pin "5") (pinfunction "5_5") (pintype "passive"))
      (node (ref "U1") (pin "6") (pinfunction "GPIO2/RTC_GPIO2/TOUCH2/ADC1_CH1_6") (pintype "passive"))
    )
    (net (code "26") (name "/GPIO3") (class "Default")
      (node (ref "J1") (pin "6") (pinfunction "6_6") (pintype "passive"))
      (node (ref "U1") (pin "7") (pinfunction "GPIO3/RTC_GPIO3/TOUCH3/ADC1_CH2_7") (pintype "passive"))
    )
    (net (code "27") (name "/GPIO4") (class "Default")
      (node (ref "J1") (pin "7") (pinfunction "7_7") (pintype "passive"))
      (node (ref "U1") (pin "8") (pinfunction "GPIO4/RTC_GPIO4/TOUCH4/ADC1_CH3_8") (pintype "passive"))
    )
    (net (code "28") (name "/GPIO5") (class "Default")
      (node (ref "J1") (pin "8") (pinfunction "8_8") (pintype "passive"))
      (node (ref "U1") (pin "9") (pinfunction "GPIO5/RTC_GPIO5/TOUCH5/ADC1_CH4_9") (pintype "passive"))
    )
    (net (code "29") (name "/GPIO6") (class "Default")
      (node (ref "J1") (pin "9") (pinfunction "9_9") (pintype "passive"))
      (node (ref "U1") (pin "10") (pinfunction "GPIO6/RTC_GPIO6/TOUCH6/ADC1_CH5_10") (pintype "passive"))
    )
    (net (code "30") (name "/GPIO7") (class "Default")
      (node (ref "J1") (pin "10") (pinfunction "10_10") (pintype "passive"))
      (node (ref "U1") (pin "11") (pinfunction "GPIO7/RTC_GPIO7/TOUCH7/ADC1_CH6_11") (pintype "passive"))
    )
    (net (code "31") (name "/GPIO8") (class "Default")
      (node (ref "J1") (pin "11") (pinfunction "11_11") (pintype "passive"))
      (node (ref "U1") (pin "12") (pinfunction "GPIO8/RTC_GPIO8/TOUCH8/ADC1_CH7/SUBSPICS1_12") (pintype "passive"))
    )
    (net (code "32") (name "/GPIO9") (class "Default")
      (node (ref "J1") (pin "12") (pinfunction "12_12") (pintype "passive"))
      (node (ref "U1") (pin "13") (pinfunction "GPIO9/RTC_GPIO9/TOUCH9/ADC1_CH8/FSPIHD/SUBSPIHD_13") (pintype "passive"))
    )
    (net (code "33") (name "/GPIO10") (class "Default")
      (node (ref "J1") (pin "13") (pinfunction "13_13") (pintype "passive"))
      (node (ref "U1") (pin "14") (pinfunction "GPIO10/RTC_GPIO10/TOUCH10/ADC1_CH9/FSPICS0/FSPIIO4/SUBSPICS0_14") (pintype "passive"))
    )
    (net (code "34") (name "/GPIO11") (class "Default")
      (node (ref "J1") (pin "14") (pinfunction "14_14") (pintype "passive"))
      (node (ref "U1") (pin "15") (pinfunction "GPIO11/RTC_GPIO11/TOUCH11/ADC2_CH0/FSPID/FSPIIO5/SUBSPID_15") (pintype "passive"))
    )
    (net (code "35") (name "/GPIO12") (class "Default")
      (node (ref "J1") (pin "15") (pinfunction "15_15") (pintype "passive"))
      (node (ref "U1") (pin "16") (pinfunction "GPIO12/RTC_GPIO12/TOUCH12/ADC2_CH1/FSPICLK/FSPIIO6/SUBSPICLK_16") (pintype "passive"))
    )
    (net (code "36") (name "/GPIO13") (class "Default")
      (node (ref "J1") (pin "16") (pinfunction "16_16") (pintype "passive"))
      (node (ref "U1") (pin "17") (pinfunction "GPIO13/RTC_GPIO13/TOUCH13/ADC2_CH2/FSPIQ/FSPIIO7/SUBSPIQ_17") (pintype "passive"))
    )
    (net (code "37") (name "/GPIO14") (class "Default")
      (node (ref "J1") (pin "17") (pinfunction "17_17") (pintype "passive"))
      (node (ref "U1") (pin "18") (pinfunction "GPIO14/RTC_GPIO14/TOUCH14/ADC2_CH3/FSPIWP/FSPIDQS/SUBSPIWP_18") (pintype "passive"))
    )
    (net (code "38") (name "/GPIO15") (class "Default")
      (node (ref "J1") (pin "18") (pinfunction "18_18") (pintype "passive"))
      (node (ref "U1") (pin "19") (pinfunction "GPIO15/RTC_GPIO15/U0RTS/ADC2_CH4/XTAL_32K_P_19") (pintype "passive"))
    )
    (net (code "39") (name "/GPIO16") (class "Default")
      (node (ref "J1") (pin "19") (pinfunction "19_19") (pintype "passive"))
      (node (ref "U1") (pin "20") (pinfunction "GPIO16/RTC_GPIO16/U0CTS/ADC2_CH5/XTAL_32K_N_20") (pintype "passive"))
    )
    (net (code "40") (name "/GPIO17") (class "Default")
      (node (ref "J1") (pin "20") (pinfunction "20_20") (pintype "passive"))
      (node (ref "U1") (pin "21") (pinfunction "GPIO17/RTC_GPIO17/U1TXD/ADC2_CH6_21") (pintype "passive"))
    )
    (net (code "41") (name "/GPIO18") (class "Default")
      (node (ref "J1") (pin "21") (pinfunction "21_21") (pintype "passive"))
      (node (ref "U1") (pin "22") (pinfunction "GPIO18/RTC_GPIO18/U1RXD/ADC2_CH7/CLK_OUT3_22") (pintype "passive"))
    )
    (net (code "42") (name "/GPIO21") (class "Default")
      (node (ref "J2") (pin "19") (pinfunction "19_19") (pintype "passive"))
      (node (ref "U1") (pin "25") (pinfunction "GPIO21/RTC_GPIO21_25") (pintype "passive"))
    )
    (net (code "43") (name "/GPIO26") (class "Default")
      (node (ref "J2") (pin "18") (pinfunction "18_18") (pintype "passive"))
      (node (ref "U1") (pin "26") (pinfunction "GPIO26/SPICS1_26") (pintype "passive"))
    )
    (net (code "44") (name "/GPIO33") (class "Default")
      (node (ref "J2") (pin "17") (pinfunction "17_17") (pintype "passive"))
      (node (ref "U1") (pin "28") (pinfunction "GPIO33/SPIIO4/FSPIHD/SUBSPIHD_28") (pintype "passive"))
    )
    (net (code "45") (name "/GPIO34") (class "Default")
      (node (ref "J2") (pin "16") (pinfunction "16_16") (pintype "passive"))
      (node (ref "U1") (pin "29") (pinfunction "GPIO34/SPIIO5/FSPICS0/SUBSPICS0_29") (pintype "passive"))
    )
    (net (code "46") (name "/GPIO35") (class "Default")
      (node (ref "J2") (pin "15") (pinfunction "15_15") (pintype "passive"))
      (node (ref "U1") (pin "31") (pinfunction "GPIO35/SPIIO6/FSPID/SUBSPID_31") (pintype "passive"))
    )
    (net (code "47") (name "/GPIO36") (class "Default")
      (node (ref "J2") (pin "14") (pinfunction "14_14") (pintype "passive"))
      (node (ref "U1") (pin "32") (pinfunction "GPIO36/SPIIO7/FSPICLK/SUBSPICLK_32") (pintype "passive"))
    )
    (net (code "48") (name "/GPIO37") (class "Default")
      (node (ref "J2") (pin "13") (pinfunction "13_13") (pintype "passive"))
      (node (ref "U1") (pin "33") (pinfunction "GPIO37/SPIDQS/FSPIQ/SUBSPIQ_33") (pintype "passive"))
    )
    (net (code "49") (name "/GPIO38") (class "Default")
      (node (ref "J2") (pin "12") (pinfunction "12_12") (pintype "passive"))
      (node (ref "U1") (pin "34") (pinfunction "GPIO38/FSPIWP/SUBSPIWP_34") (pintype "passive"))
    )
    (net (code "50") (name "/GPIO39") (class "Default")
      (node (ref "J2") (pin "11") (pinfunction "11_11") (pintype "passive"))
      (node (ref "U1") (pin "35") (pinfunction "MTCK/GPIO39/CLK_OUT3/SUBSPICS1_35") (pintype "passive"))
    )
    (net (code "51") (name "/GPIO40") (class "Default")
      (node (ref "J2") (pin "10") (pinfunction "10_10") (pintype "passive"))
      (node (ref "U1") (pin "36") (pinfunction "MTDO/GPIO40/CLK_OUT2_36") (pintype "passive"))
    )
    (net (code "52") (name "/GPIO41") (class "Default")
      (node (ref "J2") (pin "9") (pinfunction "9_9") (pintype "passive"))
      (node (ref "U1") (pin "37") (pinfunction "MTDI/GPIO41/CLK_OUT1_37") (pintype "passive"))
    )
    (net (code "53") (name "/GPIO42") (class "Default")
      (node (ref "J2") (pin "8") (pinfunction "8_8") (pintype "passive"))
      (node (ref "U1") (pin "38") (pinfunction "MTMS/GPIO42_38") (pintype "passive"))
    )
    (net (code "54") (name "/GPIO45") (class "Default")
      (node (ref "J2") (pin "5") (pinfunction "5_5") (pintype "passive"))
      (node (ref "U1") (pin "41") (pinfunction "GPIO45_41") (pintype "passive"))
    )
    (net (code "55") (name "/GPIO46") (class "Default")
      (node (ref "J2") (pin "4") (pinfunction "4_4") (pintype "passive"))
      (node (ref "U1") (pin "44") (pinfunction "GPIO46_44") (pintype "passive"))
    )
    (net (code "56") (name "/GPIO47") (class "Default")
      (node (ref "J2") (pin "23") (pinfunction "23_23") (pintype "passive"))
      (node (ref "U1") (pin "27") (pinfunction "GPIO47/SPICLK_P_DIFF/SUBSPICLK_P_DIFF_27") (pintype "passive"))
    )
    (net (code "57") (name "/GPIO48") (class "Default")
      (node (ref "J2") (pin "22") (pinfunction "22_22") (pintype "passive"))
      (node (ref "U1") (pin "30") (pinfunction "GPIO48/SPICLK_N_DIFF/SUBSPICLK_N_DIFF_30") (pintype "passive"))
    )
    (net (code "58") (name "/RTS_FTDI") (class "Default")
      (node (ref "Q1") (pin "2") (pinfunction "E_2") (pintype "passive"))
      (node (ref "R18") (pin "1") (pinfunction "1_1") (pintype "passive"))
      (node (ref "U2") (pin "19") (pinfunction "~{RTS}_19") (pintype "passive"))
    )
    (net (code "59") (name "/RXD_FTDI") (class "Default")
      (node (ref "R19") (pin "2") (pinfunction "2_2") (pintype "passive"))
      (node (ref "U2") (pin "1") (pinfunction "RXD_1") (pintype "passive"))
    )
    (net (code "60") (name "/TXD_FTDI") (class "Default")
      (node (ref "R20") (pin "2") (pinfunction "2_2") (pintype "passive"))
      (node (ref "U2") (pin "17") (pinfunction "TXD_17") (pintype "passive"))
    )
    (net (code "61") (name "/U0RXD") (class "Default")
      (node (ref "J2") (pin "6") (pinfunction "6_6") (pintype "passive"))
      (node (ref "R20") (pin "1") (pinfunction "1_1") (pintype "passive"))
      (node (ref "U1") (pin "40") (pinfunction "U0RXD/GPIO44/CLK_OUT2_40") (pintype "passive"))
    )
    (net (code "62") (name "/U0TXD") (class "Default")
      (node (ref "J2") (pin "7") (pinfunction "7_7") (pintype "passive"))
      (node (ref "R19") (pin "1") (pinfunction "1_1") (pintype "passive"))
      (node (ref "U1") (pin "39") (pinfunction "U0TXD/GPIO43/CLK_OUT1_39") (pintype "passive"))
    )
    (net (code "63") (name "/VBUS_SENSE") (class "Default")
      (node (ref "R10") (pin "1") (pinfunction "1_1") (pintype "passive"))
      (node (ref "R13") (pin "2") (pinfunction "2_2") (pintype "passive"))
      (node (ref "U2") (pin "16") (pinfunction "CBUS3_16") (pintype "passive"))
    )
    (net (code "64") (name "GND") (class "Default")
      (node (ref "C1") (pin "1") (pinfunction "1_1") (pintype "passive"))
      (node (ref "C10") (pin "1") (pinfunction "1_1") (pintype "passive"))
      (node (ref "C11") (pin "1") (pinfunction "1_1") (pintype "passive"))
      (node (ref "C12") (pin "1") (pinfunction "1_1") (pintype "passive"))
      (node (ref "C13") (pin "1") (pinfunction "1_1") (pintype "passive"))
      (node (ref "C14") (pin "1") (pinfunction "1_1") (pintype "passive"))
      (node (ref "C15") (pin "1") (pinfunction "1_1") (pintype "passive"))
      (node (ref "C16") (pin "1") (pinfunction "1_1") (pintype "passive"))
      (node (ref "C17") (pin "1") (pinfunction "1_1") (pintype "passive"))
      (node (ref "C2") (pin "1") (pinfunction "1_1") (pintype "passive"))
      (node (ref "C3") (pin "1") (pinfunction "1_1") (pintype "passive"))
      (node (ref "C4") (pin "1") (pinfunction "1_1") (pintype "passive"))
      (node (ref "C5") (pin "1") (pinfunction "1_1") (pintype "passive"))
      (node (ref "C6") (pin "1") (pinfunction "1_1") (pintype "passive"))
      (node (ref "C7") (pin "1") (pinfunction "1_1") (pintype "passive"))
      (node (ref "C8") (pin "1") (pinfunction "1_1") (pintype "passive"))
      (node (ref "C9") (pin "1") (pinfunction "1_1") (pintype "passive"))
      (node (ref "D1") (pin "1") (pinfunction "1_1") (pintype "passive"))
      (node (ref "D3") (pin "1") (pinfunction "1_1") (pintype "passive"))
      (node (ref "D4") (pin "1") (pinfunction "1_1") (pintype "passive"))
      (node (ref "D5") (pin "1") (pinfunction "1_1") (pintype "passive"))
      (node (ref "D6") (pin "1") (pinfunction "1_1") (pintype "passive"))
      (node (ref "D7") (pin "1") (pinfunction "1_1") (pintype "passive"))
      (node (ref "D8") (pin "1") (pinfunction "1_1") (pintype "passive"))
      (node (ref "J1") (pin "1") (pinfunction "1_1") (pintype "passive"))
      (node (ref "J1") (pin "23") (pinfunction "23_23") (pintype "passive"))
      (node (ref "J2") (pin "2") (pinfunction "2_2") (pintype "passive"))
      (node (ref "J2") (pin "24") (pinfunction "24_24") (pintype "passive"))
      (node (ref "J3") (pin "A1B12") (pinfunction "GND_A1B12_A1B12") (pintype "passive"))
      (node (ref "J3") (pin "B1A12") (pinfunction "GND_B1A12_B1A12") (pintype "passive"))
      (node (ref "J3") (pin "S1") (pinfunction "SHIELD_1_S1") (pintype "passive"))
      (node (ref "J3") (pin "S2") (pinfunction "SHIELD_2_S2") (pintype "passive"))
      (node (ref "J3") (pin "S3") (pinfunction "SHIELD_3_S3") (pintype "passive"))
      (node (ref "J3") (pin "S4") (pinfunction "SHIELD_4_S4") (pintype "passive"))
      (node (ref "J4") (pin "A1B12") (pinfunction "GND_A1B12_A1B12") (pintype "passive"))
      (node (ref "J4") (pin "B1A12") (pinfunction "GND_B1A12_B1A12") (pintype "passive"))
      (node (ref "J4") (pin "S1") (pinfunction "SHIELD_1_S1") (pintype "passive"))
      (node (ref "J4") (pin "S2") (pinfunction "SHIELD_2_S2") (pintype "passive"))
      (node (ref "J4") (pin "S3") (pinfunction "SHIELD_3_S3") (pintype "passive"))
      (node (ref "J4") (pin "S4") (pinfunction "SHIELD_4_S4") (pintype "passive"))
      (node (ref "R11") (pin "1") (pinfunction "1_1") (pintype "passive"))
      (node (ref "R12") (pin "1") (pinfunction "1_1") (pintype "passive"))
      (node (ref "R13") (pin "1") (pinfunction "1_1") (pintype "passive"))
      (node (ref "R14") (pin "1") (pinfunction "1_1") (pintype "passive"))
      (node (ref "R15") (pin "1") (pinfunction "1_1") (pintype "passive"))
      (node (ref "R9") (pin "2") (pinfunction "2_2") (pintype "passive"))
      (node (ref "SW1") (pin "3") (pinfunction "3_3") (pintype "passive"))
      (node (ref "SW1") (pin "4") (pinfunction "4_4") (pintype "passive"))
      (node (ref "SW2") (pin "3") (pinfunction "3_3") (pintype "passive"))
      (node (ref "SW2") (pin "4") (pinfunction "4_4") (pintype "passive"))
      (node (ref "U1") (pin "1") (pinfunction "GND_01_1") (pintype "passive"))
      (node (ref "U1") (pin "2") (pinfunction "GND_02_2") (pintype "passive"))
      (node (ref "U1") (pin "42") (pinfunction "GND_42") (pintype "passive"))
      (node (ref "U1") (pin "43") (pinfunction "GND_43") (pintype "passive"))
      (node (ref "U1") (pin "46") (pinfunction "GND_46_46") (pintype "passive"))
      (node (ref "U1") (pin "47") (pinfunction "GND_47_47") (pintype "passive"))
      (node (ref "U1") (pin "48") (pinfunction "GND_48_48") (pintype "passive"))
      (node (ref "U1") (pin "49") (pinfunction "GND_49_49") (pintype "passive"))
      (node (ref "U1") (pin "50") (pinfunction "GND_50_50") (pintype "passive"))
      (node (ref "U1") (pin "51") (pinfunction "GND_51_51") (pintype "passive"))
      (node (ref "U1") (pin "52") (pinfunction "GND_52_52") (pintype "passive"))
      (node (ref "U1") (pin "53") (pinfunction "GND_53_53") (pintype "passive"))
      (node (ref "U1") (pin "54") (pinfunction "GND_54_54") (pintype "passive"))
      (node (ref "U1") (pin "55") (pinfunction "GND_55_55") (pintype "passive"))
      (node (ref "U1") (pin "56") (pinfunction "GND_56_56") (pintype "passive"))
      (node (ref "U1") (pin "57") (pinfunction "GND_57_57") (pintype "passive"))
      (node (ref "U1") (pin "58") (pinfunction "GND_58_58") (pintype "passive"))
      (node (ref "U1") (pin "59") (pinfunction "GND_59_59") (pintype "passive"))
      (node (ref "U1") (pin "60") (pinfunction "GND_60_60") (pintype "passive"))
      (node (ref "U1") (pin "61") (pinfunction "GND_61_61") (pintype "passive"))
      (node (ref "U1") (pin "62") (pinfunction "GND_62_62") (pintype "passive"))
      (node (ref "U1") (pin "63") (pinfunction "GND_63_63") (pintype "passive"))
      (node (ref "U1") (pin "64") (pinfunction "GND_64_64") (pintype "passive"))
      (node (ref "U1") (pin "65") (pinfunction "GND_65_65") (pintype "passive"))
      (node (ref "U1") (pin "66") (pinfunction "GND_66_66") (pintype "passive"))
      (node (ref "U1") (pin "67") (pinfunction "GND_67_67") (pintype "passive"))
      (node (ref "U1") (pin "68") (pinfunction "GND_68_68") (pintype "passive"))
      (node (ref "U1") (pin "69") (pinfunction "GND_69_69") (pintype "passive"))
      (node (ref "U1") (pin "70") (pinfunction "GND_70_70") (pintype "passive"))
      (node (ref "U1") (pin "71") (pinfunction "GND_71_71") (pintype "passive"))
      (node (ref "U1") (pin "72") (pinfunction "GND_72_72") (pintype "passive"))
      (node (ref "U1") (pin "73") (pinfunction "GND_73_73") (pintype "passive"))
      (node (ref "U2") (pin "13") (pinfunction "GND_13") (pintype "passive"))
      (node (ref "U2") (pin "21") (pinfunction "GND_21") (pintype "passive"))
      (node (ref "U2") (pin "3") (pinfunction "GND_3") (pintype "passive"))
      (node (ref "U3") (pin "2") (pinfunction "GND_2") (pintype "passive"))
      (node (ref "U3") (pin "4") (pinfunction "GND_4") (pintype "passive"))
    )
    (net (code "65") (name "Net-(D1-Pad2)") (class "Default")
      (node (ref "D1") (pin "2") (pinfunction "2_2") (pintype "passive"))
      (node (ref "R3") (pin "1") (pinfunction "1_1") (pintype "passive"))
    )
    (net (code "66") (name "Net-(D2-Pad2)") (class "Default")
      (node (ref "D2") (pin "2") (pinfunction "2_2") (pintype "passive"))
      (node (ref "R4") (pin "1") (pinfunction "1_1") (pintype "passive"))
    )
    (net (code "67") (name "Net-(J3-CC1)") (class "Default")
      (node (ref "J3") (pin "A5") (pinfunction "CC1_A5") (pintype "passive"))
      (node (ref "R12") (pin "2") (pinfunction "2_2") (pintype "passive"))
    )
    (net (code "68") (name "Net-(J3-CC2)") (class "Default")
      (node (ref "J3") (pin "B5") (pinfunction "CC2_B5") (pintype "passive"))
      (node (ref "R11") (pin "2") (pinfunction "2_2") (pintype "passive"))
    )
    (net (code "69") (name "Net-(J4-CC1)") (class "Default")
      (node (ref "J4") (pin "A5") (pinfunction "CC1_A5") (pintype "passive"))
      (node (ref "R15") (pin "2") (pinfunction "2_2") (pintype "passive"))
    )
    (net (code "70") (name "Net-(J4-CC2)") (class "Default")
      (node (ref "J4") (pin "B5") (pinfunction "CC2_B5") (pintype "passive"))
      (node (ref "R14") (pin "2") (pinfunction "2_2") (pintype "passive"))
    )
    (net (code "71") (name "Net-(Q1-B)") (class "Default")
      (node (ref "Q1") (pin "1") (pinfunction "B_1") (pintype "passive"))
      (node (ref "R16") (pin "2") (pinfunction "2_2") (pintype "passive"))
    )
    (net (code "72") (name "Net-(Q2-B)") (class "Default")
      (node (ref "Q2") (pin "1") (pinfunction "B_1") (pintype "passive"))
      (node (ref "R18") (pin "2") (pinfunction "2_2") (pintype "passive"))
    )
    (net (code "73") (name "Net-(U2-CBUS0)") (class "Default")
      (node (ref "R9") (pin "1") (pinfunction "1_1") (pintype "passive"))
      (node (ref "U2") (pin "15") (pinfunction "CBUS0_15") (pintype "passive"))
    )
    (net (code "74") (name "unconnected-(J1-Pad24)") (class "Default")
      (node (ref "J1") (pin "24") (pinfunction "24_24") (pintype "passive+no_connect"))
    )
    (net (code "75") (name "unconnected-(J3-SBU1-PadA8)") (class "Default")
      (node (ref "J3") (pin "A8") (pinfunction "SBU1_A8") (pintype "passive+no_connect"))
    )
    (net (code "76") (name "unconnected-(J3-SBU2-PadB8)") (class "Default")
      (node (ref "J3") (pin "B8") (pinfunction "SBU2_B8") (pintype "passive+no_connect"))
    )
    (net (code "77") (name "unconnected-(J4-SBU1-PadA8)") (class "Default")
      (node (ref "J4") (pin "A8") (pinfunction "SBU1_A8") (pintype "passive+no_connect"))
    )
    (net (code "78") (name "unconnected-(J4-SBU2-PadB8)") (class "Default")
      (node (ref "J4") (pin "B8") (pinfunction "SBU2_B8") (pintype "passive+no_connect"))
    )
    (net (code "79") (name "unconnected-(U2-CBUS1-Pad14)") (class "Default")
      (node (ref "U2") (pin "14") (pinfunction "CBUS1_14") (pintype "passive+no_connect"))
    )
    (net (code "80") (name "unconnected-(U2-CBUS2-Pad7)") (class "Default")
      (node (ref "U2") (pin "7") (pinfunction "CBUS2_7") (pintype "passive+no_connect"))
    )
    (net (code "81") (name "unconnected-(U2-~{CTS}-Pad6)") (class "Default")
      (node (ref "U2") (pin "6") (pinfunction "~{CTS}_6") (pintype "passive+no_connect"))
    )
    (net (code "82") (name "unconnected-(U2-~{DCD}-Pad5)") (class "Default")
      (node (ref "U2") (pin "5") (pinfunction "~{DCD}_5") (pintype "passive+no_connect"))
    )
    (net (code "83") (name "unconnected-(U2-~{DSR}-Pad4)") (class "Default")
      (node (ref "U2") (pin "4") (pinfunction "~{DSR}_4") (pintype "passive+no_connect"))
    )
    (net (code "84") (name "unconnected-(U2-~{RI}-Pad2)") (class "Default")
      (node (ref "U2") (pin "2") (pinfunction "~{RI}_2") (pintype "passive+no_connect"))
    )
  )
)
